# led.net
KiCad netlist of a schematic drawn in Altium Designer
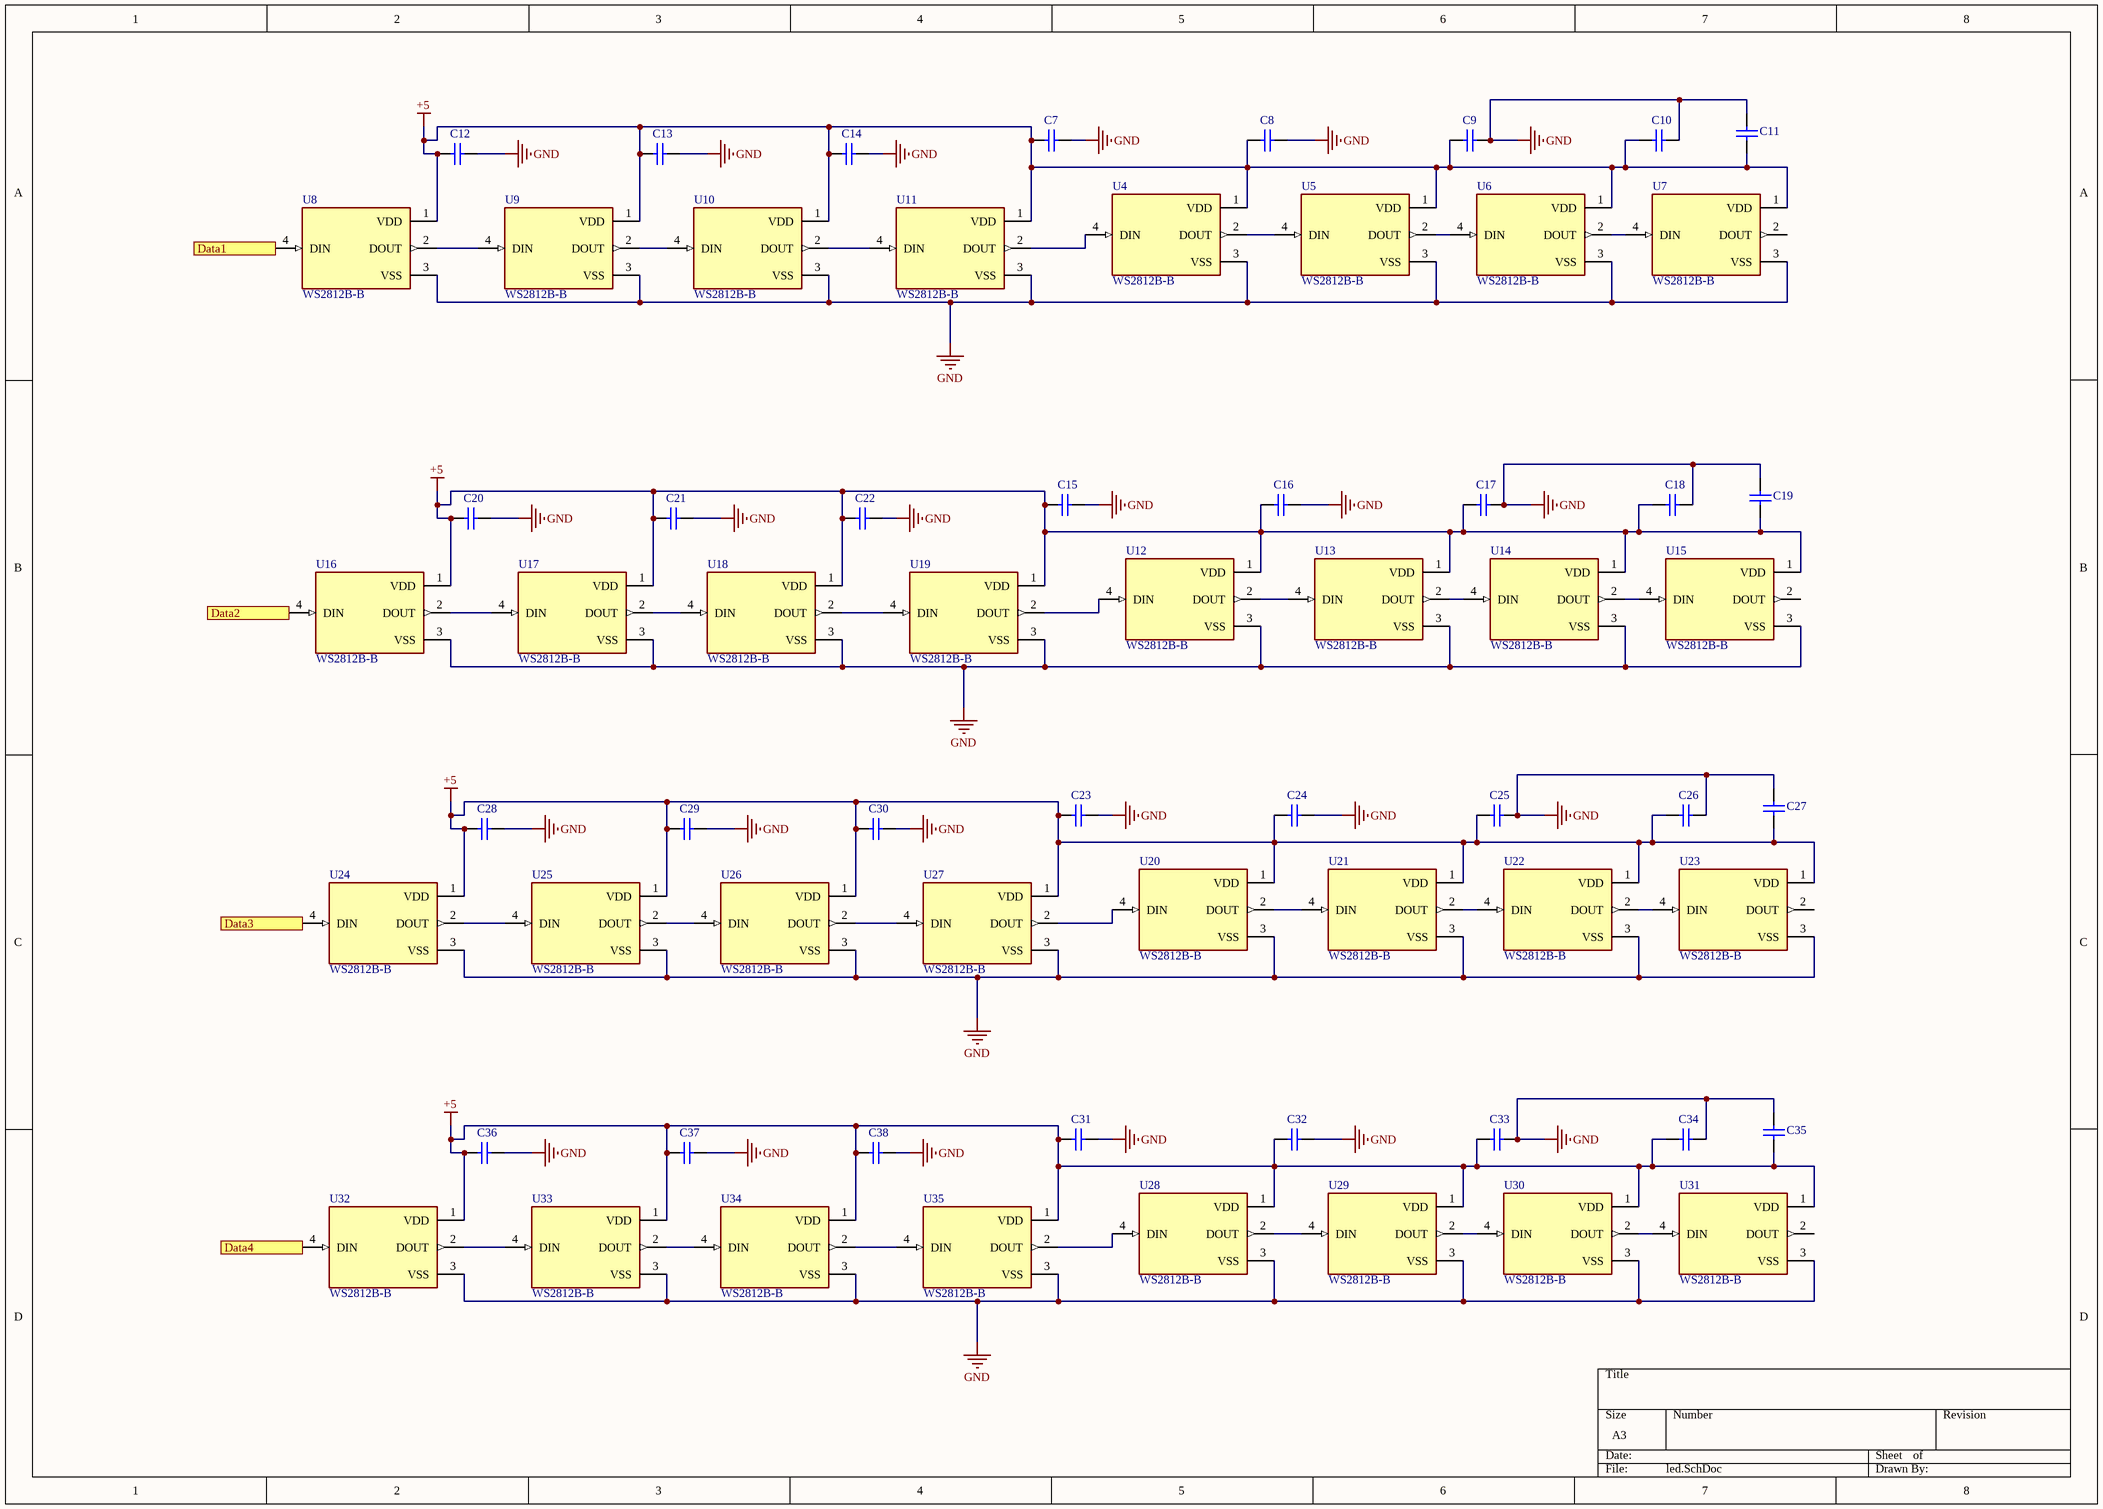
[diagram p0: led.SchDoc]

(export (version "E")
  (design (tool "Eeschema 10.0.6"))
  (components
    (comp (ref "C7")
      (value "Capacitor Ceramic")
      (footprint "C0805")
      (description "Capacitor")
      (fields (field (name "PUBLISHER") "Altium Limited"))
      (libsource (lib "My Library") (part "CapSMD"))
    )
    (comp (ref "C8")
      (value "Capacitor Ceramic")
      (footprint "C0805")
      (description "Capacitor")
      (fields (field (name "PUBLISHER") "Altium Limited"))
      (libsource (lib "My Library") (part "CapSMD"))
    )
    (comp (ref "C9")
      (value "Capacitor Ceramic")
      (footprint "C0805")
      (description "Capacitor")
      (fields (field (name "PUBLISHER") "Altium Limited"))
      (libsource (lib "My Library") (part "CapSMD"))
    )
    (comp (ref "C10")
      (value "Capacitor Ceramic")
      (footprint "C0805")
      (description "Capacitor")
      (fields (field (name "PUBLISHER") "Altium Limited"))
      (libsource (lib "My Library") (part "CapSMD"))
    )
    (comp (ref "C11")
      (value "Capacitor Ceramic")
      (footprint "C0805")
      (description "Capacitor")
      (fields (field (name "PUBLISHER") "Altium Limited"))
      (libsource (lib "My Library") (part "CapSMD"))
    )
    (comp (ref "C12")
      (value "Capacitor Ceramic")
      (footprint "C0805")
      (description "Capacitor")
      (fields (field (name "PUBLISHER") "Altium Limited"))
      (libsource (lib "My Library") (part "CapSMD"))
    )
    (comp (ref "C13")
      (value "Capacitor Ceramic")
      (footprint "C0805")
      (description "Capacitor")
      (fields (field (name "PUBLISHER") "Altium Limited"))
      (libsource (lib "My Library") (part "CapSMD"))
    )
    (comp (ref "C14")
      (value "Capacitor Ceramic")
      (footprint "C0805")
      (description "Capacitor")
      (fields (field (name "PUBLISHER") "Altium Limited"))
      (libsource (lib "My Library") (part "CapSMD"))
    )
    (comp (ref "C15")
      (value "Capacitor Ceramic")
      (footprint "C0805")
      (description "Capacitor")
      (fields (field (name "PUBLISHER") "Altium Limited"))
      (libsource (lib "My Library") (part "CapSMD"))
    )
    (comp (ref "C16")
      (value "Capacitor Ceramic")
      (footprint "C0805")
      (description "Capacitor")
      (fields (field (name "PUBLISHER") "Altium Limited"))
      (libsource (lib "My Library") (part "CapSMD"))
    )
    (comp (ref "C17")
      (value "Capacitor Ceramic")
      (footprint "C0805")
      (description "Capacitor")
      (fields (field (name "PUBLISHER") "Altium Limited"))
      (libsource (lib "My Library") (part "CapSMD"))
    )
    (comp (ref "C18")
      (value "Capacitor Ceramic")
      (footprint "C0805")
      (description "Capacitor")
      (fields (field (name "PUBLISHER") "Altium Limited"))
      (libsource (lib "My Library") (part "CapSMD"))
    )
    (comp (ref "C19")
      (value "Capacitor Ceramic")
      (footprint "C0805")
      (description "Capacitor")
      (fields (field (name "PUBLISHER") "Altium Limited"))
      (libsource (lib "My Library") (part "CapSMD"))
    )
    (comp (ref "C20")
      (value "Capacitor Ceramic")
      (footprint "C0805")
      (description "Capacitor")
      (fields (field (name "PUBLISHER") "Altium Limited"))
      (libsource (lib "My Library") (part "CapSMD"))
    )
    (comp (ref "C21")
      (value "Capacitor Ceramic")
      (footprint "C0805")
      (description "Capacitor")
      (fields (field (name "PUBLISHER") "Altium Limited"))
      (libsource (lib "My Library") (part "CapSMD"))
    )
    (comp (ref "C22")
      (value "Capacitor Ceramic")
      (footprint "C0805")
      (description "Capacitor")
      (fields (field (name "PUBLISHER") "Altium Limited"))
      (libsource (lib "My Library") (part "CapSMD"))
    )
    (comp (ref "C23")
      (value "Capacitor Ceramic")
      (footprint "C0805")
      (description "Capacitor")
      (fields (field (name "PUBLISHER") "Altium Limited"))
      (libsource (lib "My Library") (part "CapSMD"))
    )
    (comp (ref "C24")
      (value "Capacitor Ceramic")
      (footprint "C0805")
      (description "Capacitor")
      (fields (field (name "PUBLISHER") "Altium Limited"))
      (libsource (lib "My Library") (part "CapSMD"))
    )
    (comp (ref "C25")
      (value "Capacitor Ceramic")
      (footprint "C0805")
      (description "Capacitor")
      (fields (field (name "PUBLISHER") "Altium Limited"))
      (libsource (lib "My Library") (part "CapSMD"))
    )
    (comp (ref "C26")
      (value "Capacitor Ceramic")
      (footprint "C0805")
      (description "Capacitor")
      (fields (field (name "PUBLISHER") "Altium Limited"))
      (libsource (lib "My Library") (part "CapSMD"))
    )
    (comp (ref "C27")
      (value "Capacitor Ceramic")
      (footprint "C0805")
      (description "Capacitor")
      (fields (field (name "PUBLISHER") "Altium Limited"))
      (libsource (lib "My Library") (part "CapSMD"))
    )
    (comp (ref "C28")
      (value "Capacitor Ceramic")
      (footprint "C0805")
      (description "Capacitor")
      (fields (field (name "PUBLISHER") "Altium Limited"))
      (libsource (lib "My Library") (part "CapSMD"))
    )
    (comp (ref "C29")
      (value "Capacitor Ceramic")
      (footprint "C0805")
      (description "Capacitor")
      (fields (field (name "PUBLISHER") "Altium Limited"))
      (libsource (lib "My Library") (part "CapSMD"))
    )
    (comp (ref "C30")
      (value "Capacitor Ceramic")
      (footprint "C0805")
      (description "Capacitor")
      (fields (field (name "PUBLISHER") "Altium Limited"))
      (libsource (lib "My Library") (part "CapSMD"))
    )
    (comp (ref "C31")
      (value "Capacitor Ceramic")
      (footprint "C0805")
      (description "Capacitor")
      (fields (field (name "PUBLISHER") "Altium Limited"))
      (libsource (lib "My Library") (part "CapSMD"))
    )
    (comp (ref "C32")
      (value "Capacitor Ceramic")
      (footprint "C0805")
      (description "Capacitor")
      (fields (field (name "PUBLISHER") "Altium Limited"))
      (libsource (lib "My Library") (part "CapSMD"))
    )
    (comp (ref "C33")
      (value "Capacitor Ceramic")
      (footprint "C0805")
      (description "Capacitor")
      (fields (field (name "PUBLISHER") "Altium Limited"))
      (libsource (lib "My Library") (part "CapSMD"))
    )
    (comp (ref "C34")
      (value "Capacitor Ceramic")
      (footprint "C0805")
      (description "Capacitor")
      (fields (field (name "PUBLISHER") "Altium Limited"))
      (libsource (lib "My Library") (part "CapSMD"))
    )
    (comp (ref "C35")
      (value "Capacitor Ceramic")
      (footprint "C0805")
      (description "Capacitor")
      (fields (field (name "PUBLISHER") "Altium Limited"))
      (libsource (lib "My Library") (part "CapSMD"))
    )
    (comp (ref "C36")
      (value "Capacitor Ceramic")
      (footprint "C0805")
      (description "Capacitor")
      (fields (field (name "PUBLISHER") "Altium Limited"))
      (libsource (lib "My Library") (part "CapSMD"))
    )
    (comp (ref "C37")
      (value "Capacitor Ceramic")
      (footprint "C0805")
      (description "Capacitor")
      (fields (field (name "PUBLISHER") "Altium Limited"))
      (libsource (lib "My Library") (part "CapSMD"))
    )
    (comp (ref "C38")
      (value "Capacitor Ceramic")
      (footprint "C0805")
      (description "Capacitor")
      (fields (field (name "PUBLISHER") "Altium Limited"))
      (libsource (lib "My Library") (part "CapSMD"))
    )
    (comp (ref "U4")
      (value "WS2812B-B")
      (footprint "LED_WS2812B-B")
      (description "Intelligent control LED integrated light source")
      (libsource (lib "WS2812B-B") (part "WS2812B-B"))
    )
    (comp (ref "U5")
      (value "WS2812B-B")
      (footprint "LED_WS2812B-B")
      (description "Intelligent control LED integrated light source")
      (libsource (lib "WS2812B-B") (part "WS2812B-B"))
    )
    (comp (ref "U6")
      (value "WS2812B-B")
      (footprint "LED_WS2812B-B")
      (description "Intelligent control LED integrated light source")
      (libsource (lib "WS2812B-B") (part "WS2812B-B"))
    )
    (comp (ref "U7")
      (value "WS2812B-B")
      (footprint "LED_WS2812B-B")
      (description "Intelligent control LED integrated light source")
      (libsource (lib "WS2812B-B") (part "WS2812B-B"))
    )
    (comp (ref "U8")
      (value "WS2812B-B")
      (footprint "LED_WS2812B-B")
      (description "Intelligent control LED integrated light source")
      (libsource (lib "WS2812B-B") (part "WS2812B-B"))
    )
    (comp (ref "U9")
      (value "WS2812B-B")
      (footprint "LED_WS2812B-B")
      (description "Intelligent control LED integrated light source")
      (libsource (lib "WS2812B-B") (part "WS2812B-B"))
    )
    (comp (ref "U10")
      (value "WS2812B-B")
      (footprint "LED_WS2812B-B")
      (description "Intelligent control LED integrated light source")
      (libsource (lib "WS2812B-B") (part "WS2812B-B"))
    )
    (comp (ref "U11")
      (value "WS2812B-B")
      (footprint "LED_WS2812B-B")
      (description "Intelligent control LED integrated light source")
      (libsource (lib "WS2812B-B") (part "WS2812B-B"))
    )
    (comp (ref "U12")
      (value "WS2812B-B")
      (footprint "LED_WS2812B-B")
      (description "Intelligent control LED integrated light source")
      (libsource (lib "WS2812B-B") (part "WS2812B-B"))
    )
    (comp (ref "U13")
      (value "WS2812B-B")
      (footprint "LED_WS2812B-B")
      (description "Intelligent control LED integrated light source")
      (libsource (lib "WS2812B-B") (part "WS2812B-B"))
    )
    (comp (ref "U14")
      (value "WS2812B-B")
      (footprint "LED_WS2812B-B")
      (description "Intelligent control LED integrated light source")
      (libsource (lib "WS2812B-B") (part "WS2812B-B"))
    )
    (comp (ref "U15")
      (value "WS2812B-B")
      (footprint "LED_WS2812B-B")
      (description "Intelligent control LED integrated light source")
      (libsource (lib "WS2812B-B") (part "WS2812B-B"))
    )
    (comp (ref "U16")
      (value "WS2812B-B")
      (footprint "LED_WS2812B-B")
      (description "Intelligent control LED integrated light source")
      (libsource (lib "WS2812B-B") (part "WS2812B-B"))
    )
    (comp (ref "U17")
      (value "WS2812B-B")
      (footprint "LED_WS2812B-B")
      (description "Intelligent control LED integrated light source")
      (libsource (lib "WS2812B-B") (part "WS2812B-B"))
    )
    (comp (ref "U18")
      (value "WS2812B-B")
      (footprint "LED_WS2812B-B")
      (description "Intelligent control LED integrated light source")
      (libsource (lib "WS2812B-B") (part "WS2812B-B"))
    )
    (comp (ref "U19")
      (value "WS2812B-B")
      (footprint "LED_WS2812B-B")
      (description "Intelligent control LED integrated light source")
      (libsource (lib "WS2812B-B") (part "WS2812B-B"))
    )
    (comp (ref "U20")
      (value "WS2812B-B")
      (footprint "LED_WS2812B-B")
      (description "Intelligent control LED integrated light source")
      (libsource (lib "WS2812B-B") (part "WS2812B-B"))
    )
    (comp (ref "U21")
      (value "WS2812B-B")
      (footprint "LED_WS2812B-B")
      (description "Intelligent control LED integrated light source")
      (libsource (lib "WS2812B-B") (part "WS2812B-B"))
    )
    (comp (ref "U22")
      (value "WS2812B-B")
      (footprint "LED_WS2812B-B")
      (description "Intelligent control LED integrated light source")
      (libsource (lib "WS2812B-B") (part "WS2812B-B"))
    )
    (comp (ref "U23")
      (value "WS2812B-B")
      (footprint "LED_WS2812B-B")
      (description "Intelligent control LED integrated light source")
      (libsource (lib "WS2812B-B") (part "WS2812B-B"))
    )
    (comp (ref "U24")
      (value "WS2812B-B")
      (footprint "LED_WS2812B-B")
      (description "Intelligent control LED integrated light source")
      (libsource (lib "WS2812B-B") (part "WS2812B-B"))
    )
    (comp (ref "U25")
      (value "WS2812B-B")
      (footprint "LED_WS2812B-B")
      (description "Intelligent control LED integrated light source")
      (libsource (lib "WS2812B-B") (part "WS2812B-B"))
    )
    (comp (ref "U26")
      (value "WS2812B-B")
      (footprint "LED_WS2812B-B")
      (description "Intelligent control LED integrated light source")
      (libsource (lib "WS2812B-B") (part "WS2812B-B"))
    )
    (comp (ref "U27")
      (value "WS2812B-B")
      (footprint "LED_WS2812B-B")
      (description "Intelligent control LED integrated light source")
      (libsource (lib "WS2812B-B") (part "WS2812B-B"))
    )
    (comp (ref "U28")
      (value "WS2812B-B")
      (footprint "LED_WS2812B-B")
      (description "Intelligent control LED integrated light source")
      (libsource (lib "WS2812B-B") (part "WS2812B-B"))
    )
    (comp (ref "U29")
      (value "WS2812B-B")
      (footprint "LED_WS2812B-B")
      (description "Intelligent control LED integrated light source")
      (libsource (lib "WS2812B-B") (part "WS2812B-B"))
    )
    (comp (ref "U30")
      (value "WS2812B-B")
      (footprint "LED_WS2812B-B")
      (description "Intelligent control LED integrated light source")
      (libsource (lib "WS2812B-B") (part "WS2812B-B"))
    )
    (comp (ref "U31")
      (value "WS2812B-B")
      (footprint "LED_WS2812B-B")
      (description "Intelligent control LED integrated light source")
      (libsource (lib "WS2812B-B") (part "WS2812B-B"))
    )
    (comp (ref "U32")
      (value "WS2812B-B")
      (footprint "LED_WS2812B-B")
      (description "Intelligent control LED integrated light source")
      (libsource (lib "WS2812B-B") (part "WS2812B-B"))
    )
    (comp (ref "U33")
      (value "WS2812B-B")
      (footprint "LED_WS2812B-B")
      (description "Intelligent control LED integrated light source")
      (libsource (lib "WS2812B-B") (part "WS2812B-B"))
    )
    (comp (ref "U34")
      (value "WS2812B-B")
      (footprint "LED_WS2812B-B")
      (description "Intelligent control LED integrated light source")
      (libsource (lib "WS2812B-B") (part "WS2812B-B"))
    )
    (comp (ref "U35")
      (value "WS2812B-B")
      (footprint "LED_WS2812B-B")
      (description "Intelligent control LED integrated light source")
      (libsource (lib "WS2812B-B") (part "WS2812B-B"))
    )
  )
  (nets
    (net (code "1") (name "+5") (class "Default")
      (node (ref "C10") (pin "1") (pinfunction "1_1") (pintype "passive"))
      (node (ref "C11") (pin "1") (pinfunction "1_1") (pintype "passive"))
      (node (ref "C12") (pin "1") (pinfunction "1_1") (pintype "passive"))
      (node (ref "C13") (pin "1") (pinfunction "1_1") (pintype "passive"))
      (node (ref "C14") (pin "1") (pinfunction "1_1") (pintype "passive"))
      (node (ref "C15") (pin "1") (pinfunction "1_1") (pintype "passive"))
      (node (ref "C16") (pin "1") (pinfunction "1_1") (pintype "passive"))
      (node (ref "C17") (pin "1") (pinfunction "1_1") (pintype "passive"))
      (node (ref "C18") (pin "1") (pinfunction "1_1") (pintype "passive"))
      (node (ref "C19") (pin "1") (pinfunction "1_1") (pintype "passive"))
      (node (ref "C20") (pin "1") (pinfunction "1_1") (pintype "passive"))
      (node (ref "C21") (pin "1") (pinfunction "1_1") (pintype "passive"))
      (node (ref "C22") (pin "1") (pinfunction "1_1") (pintype "passive"))
      (node (ref "C23") (pin "1") (pinfunction "1_1") (pintype "passive"))
      (node (ref "C24") (pin "1") (pinfunction "1_1") (pintype "passive"))
      (node (ref "C25") (pin "1") (pinfunction "1_1") (pintype "passive"))
      (node (ref "C26") (pin "1") (pinfunction "1_1") (pintype "passive"))
      (node (ref "C27") (pin "1") (pinfunction "1_1") (pintype "passive"))
      (node (ref "C28") (pin "1") (pinfunction "1_1") (pintype "passive"))
      (node (ref "C29") (pin "1") (pinfunction "1_1") (pintype "passive"))
      (node (ref "C30") (pin "1") (pinfunction "1_1") (pintype "passive"))
      (node (ref "C31") (pin "1") (pinfunction "1_1") (pintype "passive"))
      (node (ref "C32") (pin "1") (pinfunction "1_1") (pintype "passive"))
      (node (ref "C33") (pin "1") (pinfunction "1_1") (pintype "passive"))
      (node (ref "C34") (pin "1") (pinfunction "1_1") (pintype "passive"))
      (node (ref "C35") (pin "1") (pinfunction "1_1") (pintype "passive"))
      (node (ref "C36") (pin "1") (pinfunction "1_1") (pintype "passive"))
      (node (ref "C37") (pin "1") (pinfunction "1_1") (pintype "passive"))
      (node (ref "C38") (pin "1") (pinfunction "1_1") (pintype "passive"))
      (node (ref "C7") (pin "1") (pinfunction "1_1") (pintype "passive"))
      (node (ref "C8") (pin "1") (pinfunction "1_1") (pintype "passive"))
      (node (ref "C9") (pin "1") (pinfunction "1_1") (pintype "passive"))
      (node (ref "U10") (pin "1") (pinfunction "VDD_1") (pintype "power_in"))
      (node (ref "U11") (pin "1") (pinfunction "VDD_1") (pintype "power_in"))
      (node (ref "U12") (pin "1") (pinfunction "VDD_1") (pintype "power_in"))
      (node (ref "U13") (pin "1") (pinfunction "VDD_1") (pintype "power_in"))
      (node (ref "U14") (pin "1") (pinfunction "VDD_1") (pintype "power_in"))
      (node (ref "U15") (pin "1") (pinfunction "VDD_1") (pintype "power_in"))
      (node (ref "U16") (pin "1") (pinfunction "VDD_1") (pintype "power_in"))
      (node (ref "U17") (pin "1") (pinfunction "VDD_1") (pintype "power_in"))
      (node (ref "U18") (pin "1") (pinfunction "VDD_1") (pintype "power_in"))
      (node (ref "U19") (pin "1") (pinfunction "VDD_1") (pintype "power_in"))
      (node (ref "U20") (pin "1") (pinfunction "VDD_1") (pintype "power_in"))
      (node (ref "U21") (pin "1") (pinfunction "VDD_1") (pintype "power_in"))
      (node (ref "U22") (pin "1") (pinfunction "VDD_1") (pintype "power_in"))
      (node (ref "U23") (pin "1") (pinfunction "VDD_1") (pintype "power_in"))
      (node (ref "U24") (pin "1") (pinfunction "VDD_1") (pintype "power_in"))
      (node (ref "U25") (pin "1") (pinfunction "VDD_1") (pintype "power_in"))
      (node (ref "U26") (pin "1") (pinfunction "VDD_1") (pintype "power_in"))
      (node (ref "U27") (pin "1") (pinfunction "VDD_1") (pintype "power_in"))
      (node (ref "U28") (pin "1") (pinfunction "VDD_1") (pintype "power_in"))
      (node (ref "U29") (pin "1") (pinfunction "VDD_1") (pintype "power_in"))
      (node (ref "U30") (pin "1") (pinfunction "VDD_1") (pintype "power_in"))
      (node (ref "U31") (pin "1") (pinfunction "VDD_1") (pintype "power_in"))
      (node (ref "U32") (pin "1") (pinfunction "VDD_1") (pintype "power_in"))
      (node (ref "U33") (pin "1") (pinfunction "VDD_1") (pintype "power_in"))
      (node (ref "U34") (pin "1") (pinfunction "VDD_1") (pintype "power_in"))
      (node (ref "U35") (pin "1") (pinfunction "VDD_1") (pintype "power_in"))
      (node (ref "U4") (pin "1") (pinfunction "VDD_1") (pintype "power_in"))
      (node (ref "U5") (pin "1") (pinfunction "VDD_1") (pintype "power_in"))
      (node (ref "U6") (pin "1") (pinfunction "VDD_1") (pintype "power_in"))
      (node (ref "U7") (pin "1") (pinfunction "VDD_1") (pintype "power_in"))
      (node (ref "U8") (pin "1") (pinfunction "VDD_1") (pintype "power_in"))
      (node (ref "U9") (pin "1") (pinfunction "VDD_1") (pintype "power_in"))
    )
    (net (code "2") (name "/Data1") (class "Default")
      (node (ref "U8") (pin "4") (pinfunction "DIN_4") (pintype "input"))
    )
    (net (code "3") (name "/Data2") (class "Default")
      (node (ref "U16") (pin "4") (pinfunction "DIN_4") (pintype "input"))
    )
    (net (code "4") (name "/Data3") (class "Default")
      (node (ref "U24") (pin "4") (pinfunction "DIN_4") (pintype "input"))
    )
    (net (code "5") (name "/Data4") (class "Default")
      (node (ref "U32") (pin "4") (pinfunction "DIN_4") (pintype "input"))
    )
    (net (code "6") (name "GND") (class "Default")
      (node (ref "C10") (pin "2") (pinfunction "2_2") (pintype "passive"))
      (node (ref "C11") (pin "2") (pinfunction "2_2") (pintype "passive"))
      (node (ref "C12") (pin "2") (pinfunction "2_2") (pintype "passive"))
      (node (ref "C13") (pin "2") (pinfunction "2_2") (pintype "passive"))
      (node (ref "C14") (pin "2") (pinfunction "2_2") (pintype "passive"))
      (node (ref "C15") (pin "2") (pinfunction "2_2") (pintype "passive"))
      (node (ref "C16") (pin "2") (pinfunction "2_2") (pintype "passive"))
      (node (ref "C17") (pin "2") (pinfunction "2_2") (pintype "passive"))
      (node (ref "C18") (pin "2") (pinfunction "2_2") (pintype "passive"))
      (node (ref "C19") (pin "2") (pinfunction "2_2") (pintype "passive"))
      (node (ref "C20") (pin "2") (pinfunction "2_2") (pintype "passive"))
      (node (ref "C21") (pin "2") (pinfunction "2_2") (pintype "passive"))
      (node (ref "C22") (pin "2") (pinfunction "2_2") (pintype "passive"))
      (node (ref "C23") (pin "2") (pinfunction "2_2") (pintype "passive"))
      (node (ref "C24") (pin "2") (pinfunction "2_2") (pintype "passive"))
      (node (ref "C25") (pin "2") (pinfunction "2_2") (pintype "passive"))
      (node (ref "C26") (pin "2") (pinfunction "2_2") (pintype "passive"))
      (node (ref "C27") (pin "2") (pinfunction "2_2") (pintype "passive"))
      (node (ref "C28") (pin "2") (pinfunction "2_2") (pintype "passive"))
      (node (ref "C29") (pin "2") (pinfunction "2_2") (pintype "passive"))
      (node (ref "C30") (pin "2") (pinfunction "2_2") (pintype "passive"))
      (node (ref "C31") (pin "2") (pinfunction "2_2") (pintype "passive"))
      (node (ref "C32") (pin "2") (pinfunction "2_2") (pintype "passive"))
      (node (ref "C33") (pin "2") (pinfunction "2_2") (pintype "passive"))
      (node (ref "C34") (pin "2") (pinfunction "2_2") (pintype "passive"))
      (node (ref "C35") (pin "2") (pinfunction "2_2") (pintype "passive"))
      (node (ref "C36") (pin "2") (pinfunction "2_2") (pintype "passive"))
      (node (ref "C37") (pin "2") (pinfunction "2_2") (pintype "passive"))
      (node (ref "C38") (pin "2") (pinfunction "2_2") (pintype "passive"))
      (node (ref "C7") (pin "2") (pinfunction "2_2") (pintype "passive"))
      (node (ref "C8") (pin "2") (pinfunction "2_2") (pintype "passive"))
      (node (ref "C9") (pin "2") (pinfunction "2_2") (pintype "passive"))
      (node (ref "U10") (pin "3") (pinfunction "VSS_3") (pintype "power_in"))
      (node (ref "U11") (pin "3") (pinfunction "VSS_3") (pintype "power_in"))
      (node (ref "U12") (pin "3") (pinfunction "VSS_3") (pintype "power_in"))
      (node (ref "U13") (pin "3") (pinfunction "VSS_3") (pintype "power_in"))
      (node (ref "U14") (pin "3") (pinfunction "VSS_3") (pintype "power_in"))
      (node (ref "U15") (pin "3") (pinfunction "VSS_3") (pintype "power_in"))
      (node (ref "U16") (pin "3") (pinfunction "VSS_3") (pintype "power_in"))
      (node (ref "U17") (pin "3") (pinfunction "VSS_3") (pintype "power_in"))
      (node (ref "U18") (pin "3") (pinfunction "VSS_3") (pintype "power_in"))
      (node (ref "U19") (pin "3") (pinfunction "VSS_3") (pintype "power_in"))
      (node (ref "U20") (pin "3") (pinfunction "VSS_3") (pintype "power_in"))
      (node (ref "U21") (pin "3") (pinfunction "VSS_3") (pintype "power_in"))
      (node (ref "U22") (pin "3") (pinfunction "VSS_3") (pintype "power_in"))
      (node (ref "U23") (pin "3") (pinfunction "VSS_3") (pintype "power_in"))
      (node (ref "U24") (pin "3") (pinfunction "VSS_3") (pintype "power_in"))
      (node (ref "U25") (pin "3") (pinfunction "VSS_3") (pintype "power_in"))
      (node (ref "U26") (pin "3") (pinfunction "VSS_3") (pintype "power_in"))
      (node (ref "U27") (pin "3") (pinfunction "VSS_3") (pintype "power_in"))
      (node (ref "U28") (pin "3") (pinfunction "VSS_3") (pintype "power_in"))
      (node (ref "U29") (pin "3") (pinfunction "VSS_3") (pintype "power_in"))
      (node (ref "U30") (pin "3") (pinfunction "VSS_3") (pintype "power_in"))
      (node (ref "U31") (pin "3") (pinfunction "VSS_3") (pintype "power_in"))
      (node (ref "U32") (pin "3") (pinfunction "VSS_3") (pintype "power_in"))
      (node (ref "U33") (pin "3") (pinfunction "VSS_3") (pintype "power_in"))
      (node (ref "U34") (pin "3") (pinfunction "VSS_3") (pintype "power_in"))
      (node (ref "U35") (pin "3") (pinfunction "VSS_3") (pintype "power_in"))
      (node (ref "U4") (pin "3") (pinfunction "VSS_3") (pintype "power_in"))
      (node (ref "U5") (pin "3") (pinfunction "VSS_3") (pintype "power_in"))
      (node (ref "U6") (pin "3") (pinfunction "VSS_3") (pintype "power_in"))
      (node (ref "U7") (pin "3") (pinfunction "VSS_3") (pintype "power_in"))
      (node (ref "U8") (pin "3") (pinfunction "VSS_3") (pintype "power_in"))
      (node (ref "U9") (pin "3") (pinfunction "VSS_3") (pintype "power_in"))
    )
    (net (code "7") (name "Net-(U4-DOUT)") (class "Default")
      (node (ref "U4") (pin "2") (pinfunction "DOUT_2") (pintype "output"))
      (node (ref "U5") (pin "4") (pinfunction "DIN_4") (pintype "input"))
    )
    (net (code "8") (name "Net-(U5-DOUT)") (class "Default")
      (node (ref "U5") (pin "2") (pinfunction "DOUT_2") (pintype "output"))
      (node (ref "U6") (pin "4") (pinfunction "DIN_4") (pintype "input"))
    )
    (net (code "9") (name "Net-(U6-DOUT)") (class "Default")
      (node (ref "U6") (pin "2") (pinfunction "DOUT_2") (pintype "output"))
      (node (ref "U7") (pin "4") (pinfunction "DIN_4") (pintype "input"))
    )
    (net (code "10") (name "Net-(U8-DOUT)") (class "Default")
      (node (ref "U8") (pin "2") (pinfunction "DOUT_2") (pintype "output"))
      (node (ref "U9") (pin "4") (pinfunction "DIN_4") (pintype "input"))
    )
    (net (code "11") (name "Net-(U10-DIN)") (class "Default")
      (node (ref "U10") (pin "4") (pinfunction "DIN_4") (pintype "input"))
      (node (ref "U9") (pin "2") (pinfunction "DOUT_2") (pintype "output"))
    )
    (net (code "12") (name "Net-(U10-DOUT)") (class "Default")
      (node (ref "U10") (pin "2") (pinfunction "DOUT_2") (pintype "output"))
      (node (ref "U11") (pin "4") (pinfunction "DIN_4") (pintype "input"))
    )
    (net (code "13") (name "Net-(U11-DOUT)") (class "Default")
      (node (ref "U11") (pin "2") (pinfunction "DOUT_2") (pintype "output"))
      (node (ref "U4") (pin "4") (pinfunction "DIN_4") (pintype "input"))
    )
    (net (code "14") (name "Net-(U12-DIN)") (class "Default")
      (node (ref "U12") (pin "4") (pinfunction "DIN_4") (pintype "input"))
      (node (ref "U19") (pin "2") (pinfunction "DOUT_2") (pintype "output"))
    )
    (net (code "15") (name "Net-(U12-DOUT)") (class "Default")
      (node (ref "U12") (pin "2") (pinfunction "DOUT_2") (pintype "output"))
      (node (ref "U13") (pin "4") (pinfunction "DIN_4") (pintype "input"))
    )
    (net (code "16") (name "Net-(U13-DOUT)") (class "Default")
      (node (ref "U13") (pin "2") (pinfunction "DOUT_2") (pintype "output"))
      (node (ref "U14") (pin "4") (pinfunction "DIN_4") (pintype "input"))
    )
    (net (code "17") (name "Net-(U14-DOUT)") (class "Default")
      (node (ref "U14") (pin "2") (pinfunction "DOUT_2") (pintype "output"))
      (node (ref "U15") (pin "4") (pinfunction "DIN_4") (pintype "input"))
    )
    (net (code "18") (name "Net-(U16-DOUT)") (class "Default")
      (node (ref "U16") (pin "2") (pinfunction "DOUT_2") (pintype "output"))
      (node (ref "U17") (pin "4") (pinfunction "DIN_4") (pintype "input"))
    )
    (net (code "19") (name "Net-(U17-DOUT)") (class "Default")
      (node (ref "U17") (pin "2") (pinfunction "DOUT_2") (pintype "output"))
      (node (ref "U18") (pin "4") (pinfunction "DIN_4") (pintype "input"))
    )
    (net (code "20") (name "Net-(U18-DOUT)") (class "Default")
      (node (ref "U18") (pin "2") (pinfunction "DOUT_2") (pintype "output"))
      (node (ref "U19") (pin "4") (pinfunction "DIN_4") (pintype "input"))
    )
    (net (code "21") (name "Net-(U20-DIN)") (class "Default")
      (node (ref "U20") (pin "4") (pinfunction "DIN_4") (pintype "input"))
      (node (ref "U27") (pin "2") (pinfunction "DOUT_2") (pintype "output"))
    )
    (net (code "22") (name "Net-(U20-DOUT)") (class "Default")
      (node (ref "U20") (pin "2") (pinfunction "DOUT_2") (pintype "output"))
      (node (ref "U21") (pin "4") (pinfunction "DIN_4") (pintype "input"))
    )
    (net (code "23") (name "Net-(U21-DOUT)") (class "Default")
      (node (ref "U21") (pin "2") (pinfunction "DOUT_2") (pintype "output"))
      (node (ref "U22") (pin "4") (pinfunction "DIN_4") (pintype "input"))
    )
    (net (code "24") (name "Net-(U22-DOUT)") (class "Default")
      (node (ref "U22") (pin "2") (pinfunction "DOUT_2") (pintype "output"))
      (node (ref "U23") (pin "4") (pinfunction "DIN_4") (pintype "input"))
    )
    (net (code "25") (name "Net-(U24-DOUT)") (class "Default")
      (node (ref "U24") (pin "2") (pinfunction "DOUT_2") (pintype "output"))
      (node (ref "U25") (pin "4") (pinfunction "DIN_4") (pintype "input"))
    )
    (net (code "26") (name "Net-(U25-DOUT)") (class "Default")
      (node (ref "U25") (pin "2") (pinfunction "DOUT_2") (pintype "output"))
      (node (ref "U26") (pin "4") (pinfunction "DIN_4") (pintype "input"))
    )
    (net (code "27") (name "Net-(U26-DOUT)") (class "Default")
      (node (ref "U26") (pin "2") (pinfunction "DOUT_2") (pintype "output"))
      (node (ref "U27") (pin "4") (pinfunction "DIN_4") (pintype "input"))
    )
    (net (code "28") (name "Net-(U28-DIN)") (class "Default")
      (node (ref "U28") (pin "4") (pinfunction "DIN_4") (pintype "input"))
      (node (ref "U35") (pin "2") (pinfunction "DOUT_2") (pintype "output"))
    )
    (net (code "29") (name "Net-(U28-DOUT)") (class "Default")
      (node (ref "U28") (pin "2") (pinfunction "DOUT_2") (pintype "output"))
      (node (ref "U29") (pin "4") (pinfunction "DIN_4") (pintype "input"))
    )
    (net (code "30") (name "Net-(U29-DOUT)") (class "Default")
      (node (ref "U29") (pin "2") (pinfunction "DOUT_2") (pintype "output"))
      (node (ref "U30") (pin "4") (pinfunction "DIN_4") (pintype "input"))
    )
    (net (code "31") (name "Net-(U30-DOUT)") (class "Default")
      (node (ref "U30") (pin "2") (pinfunction "DOUT_2") (pintype "output"))
      (node (ref "U31") (pin "4") (pinfunction "DIN_4") (pintype "input"))
    )
    (net (code "32") (name "Net-(U32-DOUT)") (class "Default")
      (node (ref "U32") (pin "2") (pinfunction "DOUT_2") (pintype "output"))
      (node (ref "U33") (pin "4") (pinfunction "DIN_4") (pintype "input"))
    )
    (net (code "33") (name "Net-(U33-DOUT)") (class "Default")
      (node (ref "U33") (pin "2") (pinfunction "DOUT_2") (pintype "output"))
      (node (ref "U34") (pin "4") (pinfunction "DIN_4") (pintype "input"))
    )
    (net (code "34") (name "Net-(U34-DOUT)") (class "Default")
      (node (ref "U34") (pin "2") (pinfunction "DOUT_2") (pintype "output"))
      (node (ref "U35") (pin "4") (pinfunction "DIN_4") (pintype "input"))
    )
    (net (code "35") (name "unconnected-(U7-DOUT-Pad2)") (class "Default")
      (node (ref "U7") (pin "2") (pinfunction "DOUT_2") (pintype "output"))
    )
    (net (code "36") (name "unconnected-(U15-DOUT-Pad2)") (class "Default")
      (node (ref "U15") (pin "2") (pinfunction "DOUT_2") (pintype "output"))
    )
    (net (code "37") (name "unconnected-(U23-DOUT-Pad2)") (class "Default")
      (node (ref "U23") (pin "2") (pinfunction "DOUT_2") (pintype "output"))
    )
    (net (code "38") (name "unconnected-(U31-DOUT-Pad2)") (class "Default")
      (node (ref "U31") (pin "2") (pinfunction "DOUT_2") (pintype "output"))
    )
  )
)
